# LMAT_AMT_V1.net
KiCad netlist of a schematic drawn in Altium Designer
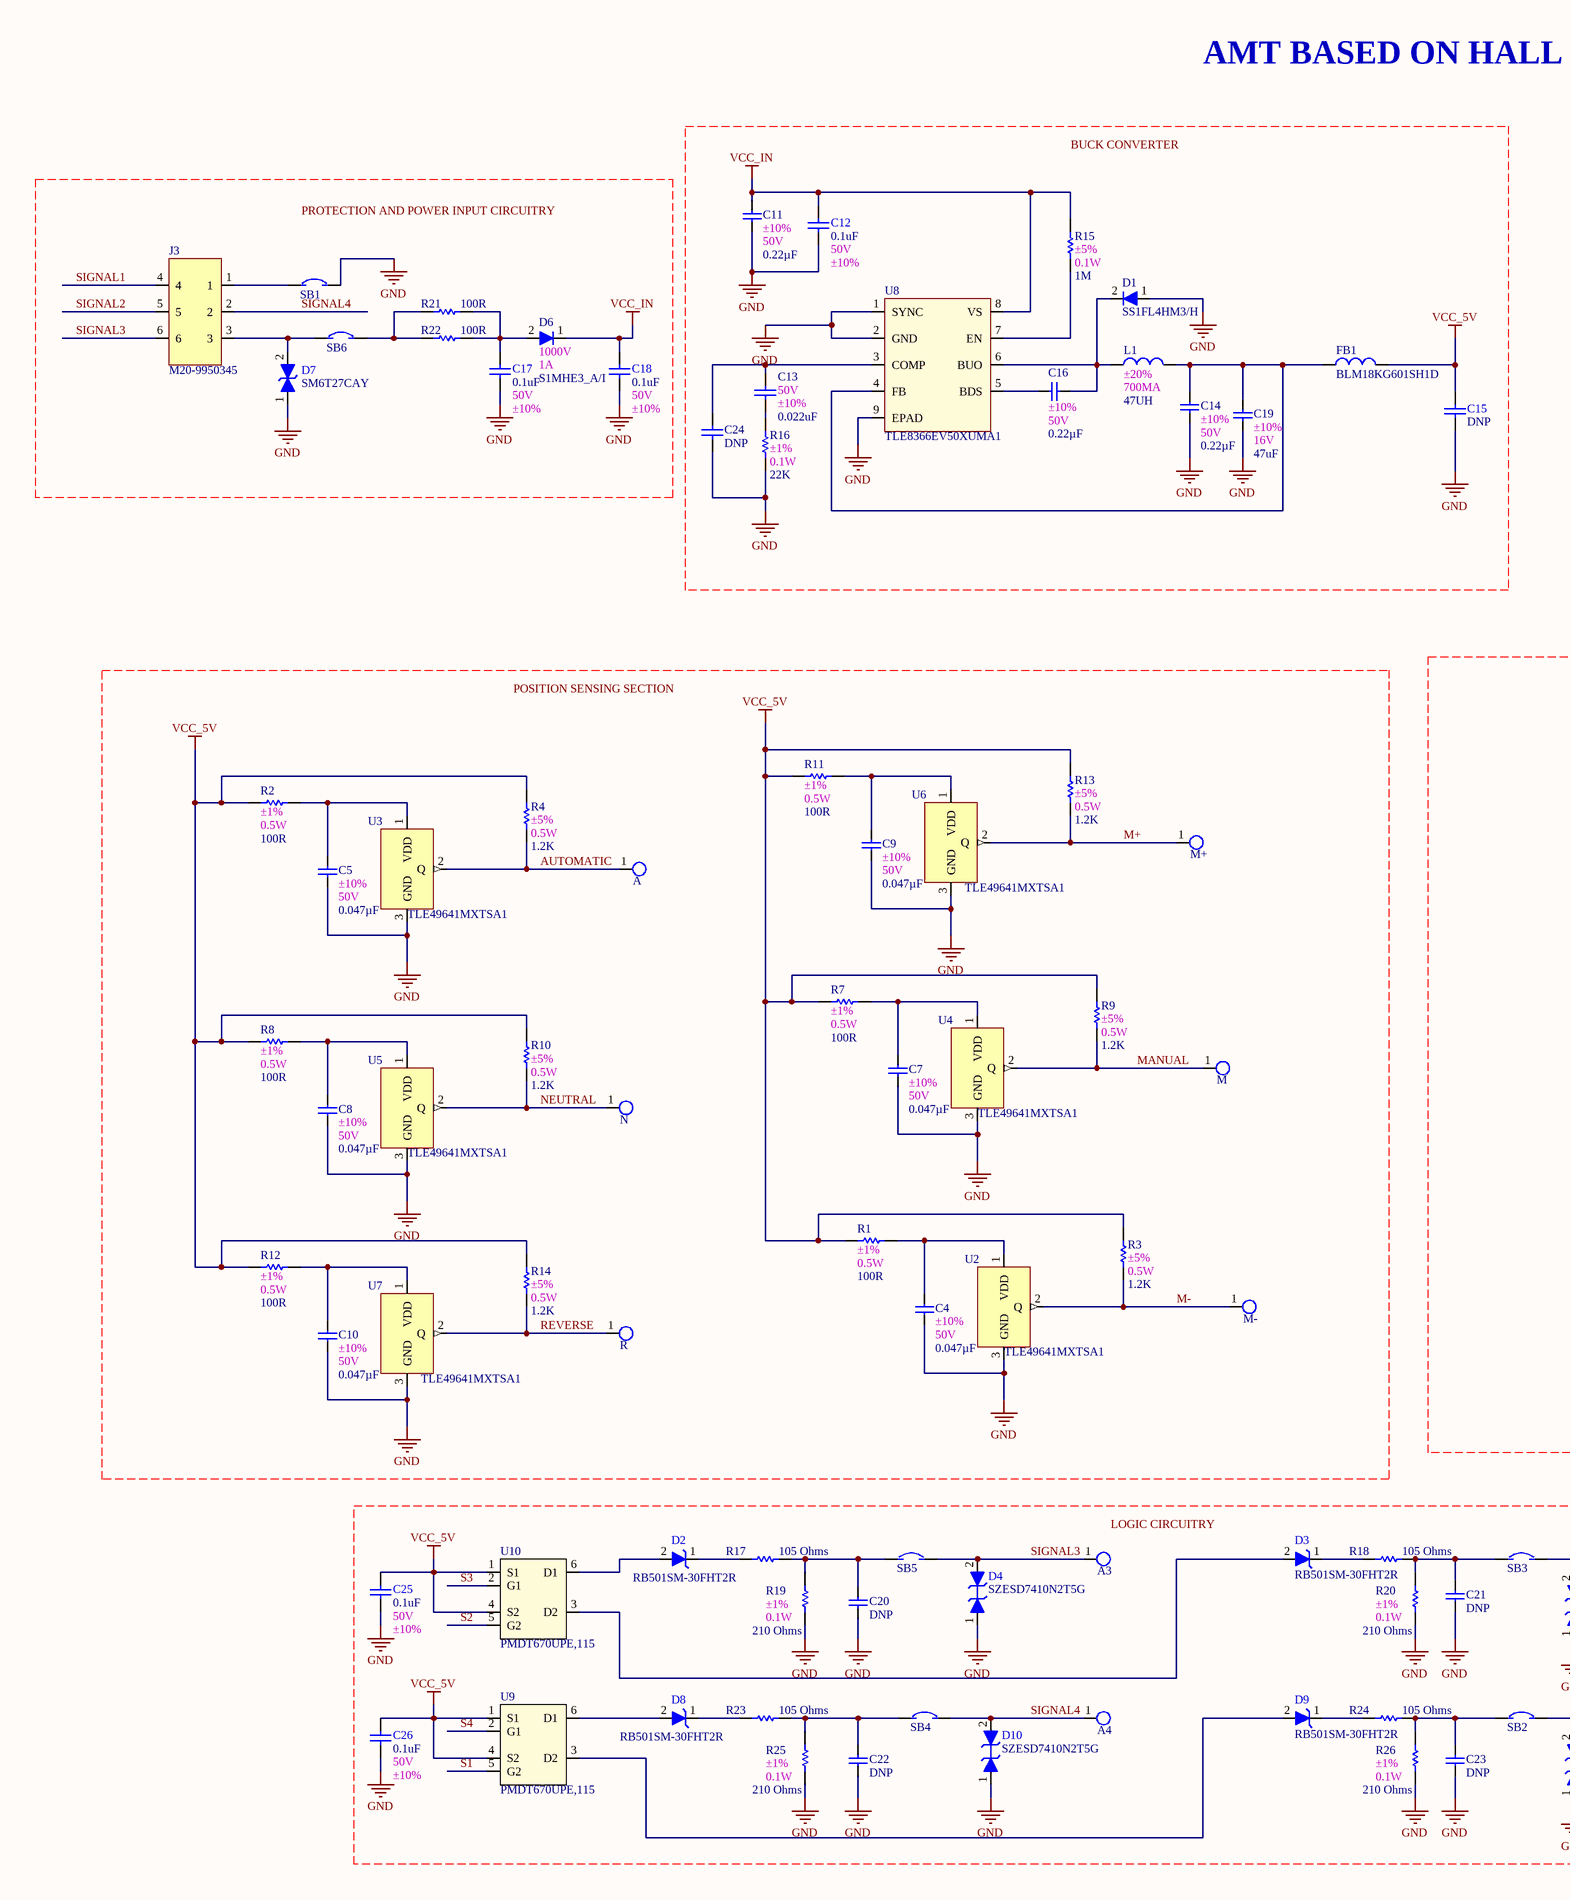
[diagram p0: LMAT_AMT_V1.SchDoc, left]
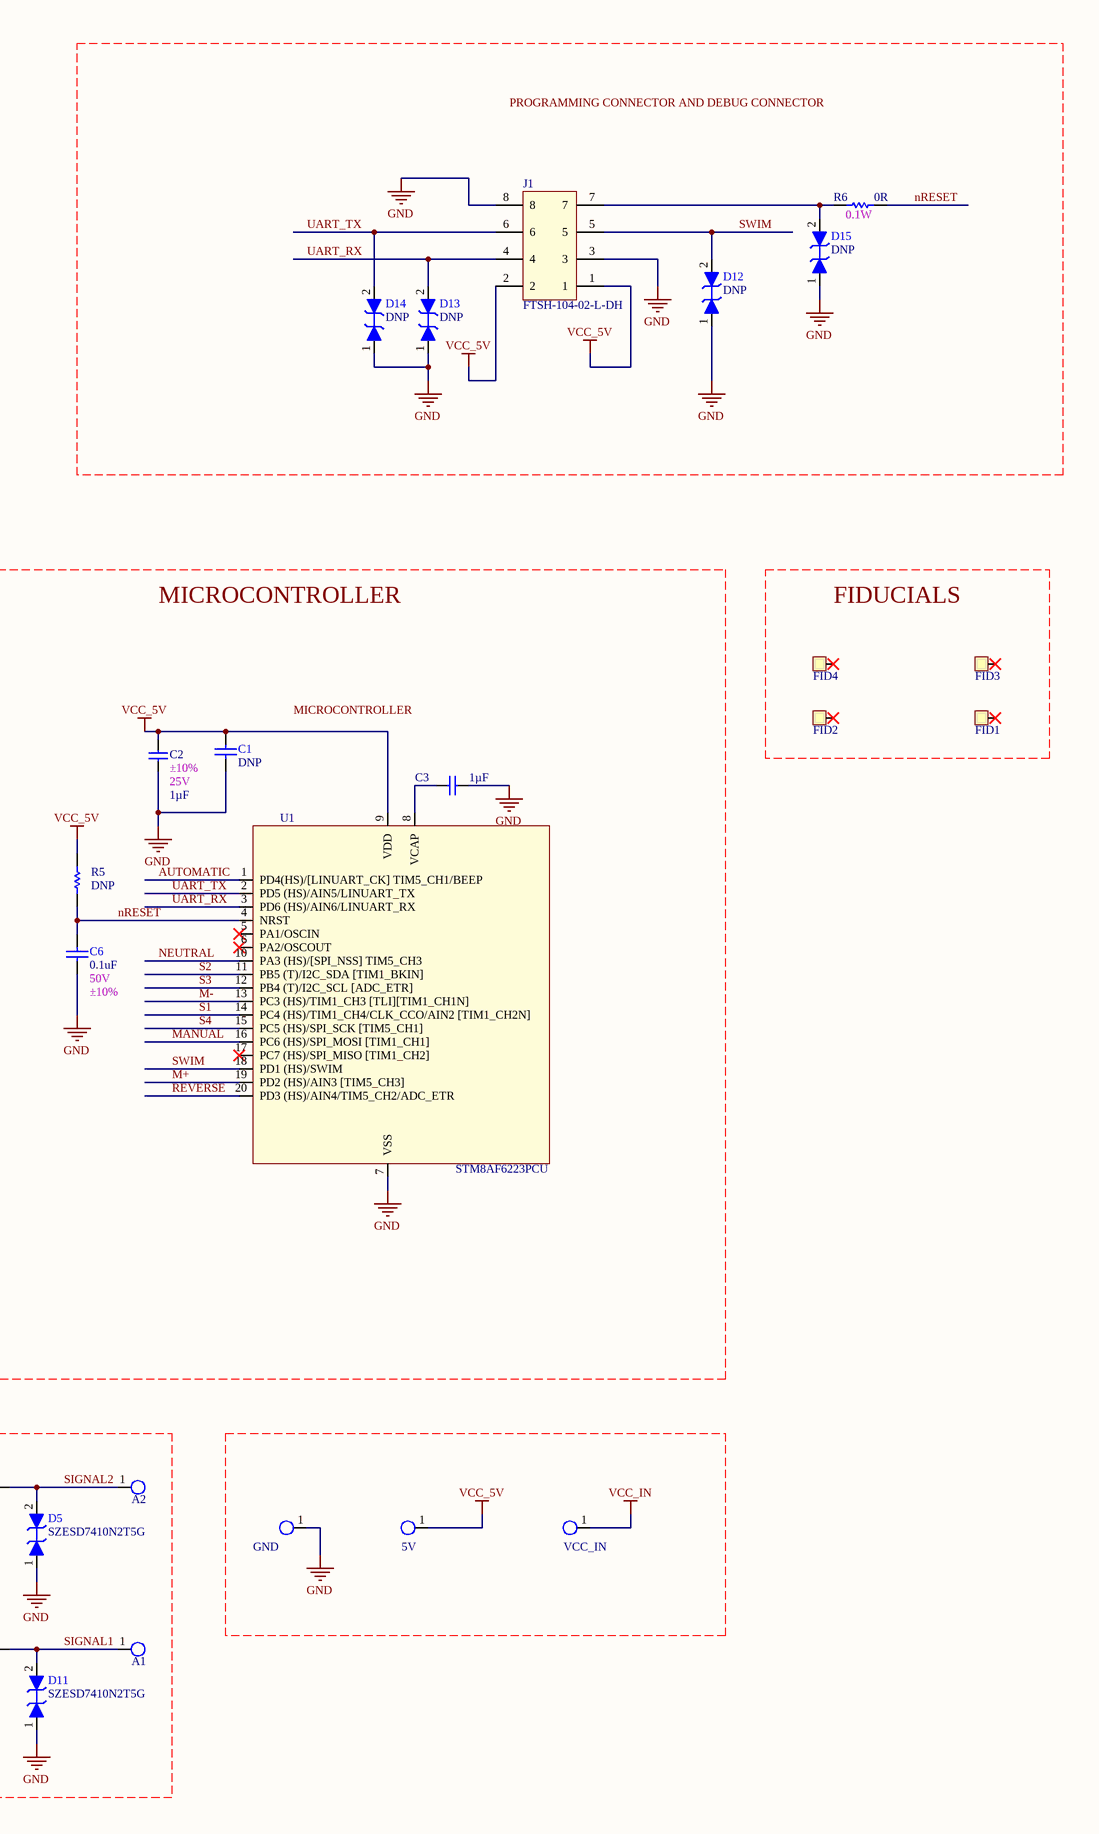
[diagram p1: LMAT_AMT_V1.SchDoc, right]

(export (version "E")
  (design (tool "Eeschema 10.0.6"))
  (components
    (comp (ref "5V")
      (value "Test Point- 35mil")
      (footprint "TP_35M_DIA")
      (fields (field (name "INTERNAL PART NUMBER") "EMS-TP35MIL-S"))
      (libsource (lib "Integrated_Master_Library") (part "EMS-TP35MIL-S"))
    )
    (comp (ref "A")
      (value "Test Point- 35mil")
      (footprint "TP_35M_DIA")
      (fields (field (name "INTERNAL PART NUMBER") "EMS-TP35MIL-S"))
      (libsource (lib "Integrated_Master_Library") (part "EMS-TP35MIL-S"))
    )
    (comp (ref "A1")
      (value "Test Point- 35mil")
      (footprint "TP_35M_DIA")
      (fields (field (name "INTERNAL PART NUMBER") "EMS-TP35MIL-S"))
      (libsource (lib "Integrated_Master_Library") (part "EMS-TP35MIL-S"))
    )
    (comp (ref "A2")
      (value "Test Point- 35mil")
      (footprint "TP_35M_DIA")
      (fields (field (name "INTERNAL PART NUMBER") "EMS-TP35MIL-S"))
      (libsource (lib "Integrated_Master_Library") (part "EMS-TP35MIL-S"))
    )
    (comp (ref "A3")
      (value "Test Point- 35mil")
      (footprint "TP_35M_DIA")
      (fields (field (name "INTERNAL PART NUMBER") "EMS-TP35MIL-S"))
      (libsource (lib "Integrated_Master_Library") (part "EMS-TP35MIL-S"))
    )
    (comp (ref "A4")
      (value "Test Point- 35mil")
      (footprint "TP_35M_DIA")
      (fields (field (name "INTERNAL PART NUMBER") "EMS-TP35MIL-S"))
      (libsource (lib "Integrated_Master_Library") (part "EMS-TP35MIL-S"))
    )
    (comp (ref "C1")
      (value "DNP")
      (footprint "SMDC0603")
      (description "CAP CER 0.1UF 50V 10% X7R 0603")
      (fields
        (field (name "MANUFACTURER PART NUMBER") "CGA3E2X7R1H104K080AA")
        (field (name "MANUFACTURER") "TDK Corporation")
      )
      (libsource (lib "Integrated_Master_Library") (part "ECA0U10K50V0-SC"))
    )
    (comp (ref "C2")
      (value "1µF")
      (footprint "SMDC0603")
      (description "CAP CER 1UF 25V X7R 0603")
      (fields
        (field (name "MANUFACTURER") "TDK Corporation")
        (field (name "VENDOR PART NUMBER") "445-173628-1-ND")
        (field (name "2ND AUXILIARY FIELD") "±10%")
        (field (name "1ST AUXILIARY FIELD") "25V")
      )
      (libsource (lib "Integrated_Master_Library (3)") (part "ECA1U00L25V0-SC"))
    )
    (comp (ref "C3")
      (value "1µF")
      (footprint "SMDC0603")
      (description "CAP CER 1UF 25V X7R 0603")
      (fields
        (field (name "MANUFACTURER") "TDK Corporation")
        (field (name "VENDOR PART NUMBER") "445-173628-1-ND")
      )
      (libsource (lib "Integrated_Master_Library (3)") (part "ECA1U00L25V0-SC"))
    )
    (comp (ref "C4")
      (value "0.047µF")
      (footprint "SMDC0603")
      (description "CAP CER 0.047UF 50V X7R 0603")
      (fields
        (field (name "MANUFACTURER") "TDK Corporation")
        (field (name "VENDOR PART NUMBER") "445-5664-1-ND")
        (field (name "2ND AUXILIARY FIELD") "±10%")
        (field (name "1ST AUXILIARY FIELD") "50V")
      )
      (libsource (lib "Integrated_Master_Library") (part "ECA47N0L50V-SC"))
    )
    (comp (ref "C5")
      (value "0.047µF")
      (footprint "SMDC0603")
      (description "CAP CER 0.047UF 50V X7R 0603")
      (fields
        (field (name "MANUFACTURER") "TDK Corporation")
        (field (name "VENDOR PART NUMBER") "445-5664-1-ND")
        (field (name "2ND AUXILIARY FIELD") "±10%")
        (field (name "1ST AUXILIARY FIELD") "50V")
      )
      (libsource (lib "Integrated_Master_Library") (part "ECA47N0L50V-SC"))
    )
    (comp (ref "C6")
      (value "0.1uF")
      (footprint "SMDC0603")
      (description "CAP CER 0.1UF 50V 10% X7R 0603")
      (fields
        (field (name "MANUFACTURER PART NUMBER") "CGA3E2X7R1H104K080AA")
        (field (name "MANUFACTURER") "TDK Corporation")
        (field (name "1ST AUXILIARY FIELD") "50V")
        (field (name "2ND AUXILIARY FIELD") "±10%")
      )
      (libsource (lib "Integrated_Master_Library") (part "ECA0U10K50V0-SC"))
    )
    (comp (ref "C7")
      (value "0.047µF")
      (footprint "SMDC0603")
      (description "CAP CER 0.047UF 50V X7R 0603")
      (fields
        (field (name "MANUFACTURER") "TDK Corporation")
        (field (name "VENDOR PART NUMBER") "445-5664-1-ND")
        (field (name "2ND AUXILIARY FIELD") "±10%")
        (field (name "1ST AUXILIARY FIELD") "50V")
      )
      (libsource (lib "Integrated_Master_Library") (part "ECA47N0L50V-SC"))
    )
    (comp (ref "C8")
      (value "0.047µF")
      (footprint "SMDC0603")
      (description "CAP CER 0.047UF 50V X7R 0603")
      (fields
        (field (name "MANUFACTURER") "TDK Corporation")
        (field (name "VENDOR PART NUMBER") "445-5664-1-ND")
        (field (name "2ND AUXILIARY FIELD") "±10%")
        (field (name "1ST AUXILIARY FIELD") "50V")
      )
      (libsource (lib "Integrated_Master_Library") (part "ECA47N0L50V-SC"))
    )
    (comp (ref "C9")
      (value "0.047µF")
      (footprint "SMDC0603")
      (description "CAP CER 0.047UF 50V X7R 0603")
      (fields
        (field (name "MANUFACTURER") "TDK Corporation")
        (field (name "VENDOR PART NUMBER") "445-5664-1-ND")
        (field (name "2ND AUXILIARY FIELD") "±10%")
        (field (name "1ST AUXILIARY FIELD") "50V")
      )
      (libsource (lib "Integrated_Master_Library") (part "ECA47N0L50V-SC"))
    )
    (comp (ref "C10")
      (value "0.047µF")
      (footprint "SMDC0603")
      (description "CAP CER 0.047UF 50V X7R 0603")
      (fields
        (field (name "MANUFACTURER") "TDK Corporation")
        (field (name "VENDOR PART NUMBER") "445-5664-1-ND")
        (field (name "2ND AUXILIARY FIELD") "±10%")
        (field (name "1ST AUXILIARY FIELD") "50V")
      )
      (libsource (lib "Integrated_Master_Library") (part "ECA47N0L50V-SC"))
    )
    (comp (ref "C11")
      (value "0.22µF")
      (footprint "SMDC0603")
      (description "CAP CER 0.22UF 50V X7R 0603")
      (fields
        (field (name "MANUFACTURER") "Murata Electronics North America")
        (field (name "VENDOR PART NUMBER") "490-14410-1-ND")
        (field (name "2ND AUXILIARY FIELD") "±10%")
        (field (name "1ST AUXILIARY FIELD") "50V")
      )
      (libsource (lib "Integrated_Master_Library (3)") (part "ECA0U22L50V0-SC"))
    )
    (comp (ref "C12")
      (value "0.1uF")
      (footprint "SMDC0603")
      (description "CAP CER 0.1UF 50V 10% X7R 0603")
      (fields
        (field (name "MANUFACTURER PART NUMBER") "CGA3E2X7R1H104K080AA")
        (field (name "MANUFACTURER") "TDK Corporation")
        (field (name "1ST AUXILIARY FIELD") "50V")
        (field (name "2ND AUXILIARY FIELD") "±10%")
      )
      (libsource (lib "Integrated_Master_Library") (part "ECA0U10K50V0-SC"))
    )
    (comp (ref "C13")
      (value "0.022uF")
      (footprint "SMDC0603")
      (description "CAP CER 0.022UF 50V 10% X7R 0603")
      (fields
        (field (name "MANUFACTURER PART NUMBER") "CGA3E2X7R1H223K080AA")
        (field (name "MANUFACTURER") "TDK Corporation")
        (field (name "1ST AUXILIARY FIELD") "50V")
        (field (name "2ND AUXILIARY FIELD") "±10%")
      )
      (libsource (lib "Integrated_Master_Library") (part "ECA0U022K50V0-SC"))
    )
    (comp (ref "C14")
      (value "0.22µF")
      (footprint "SMDC0603")
      (description "CAP CER 0.22UF 50V X7R 0603")
      (fields
        (field (name "MANUFACTURER") "Murata Electronics North America")
        (field (name "VENDOR PART NUMBER") "490-14410-1-ND")
        (field (name "2ND AUXILIARY FIELD") "±10%")
        (field (name "1ST AUXILIARY FIELD") "50V")
      )
      (libsource (lib "Integrated_Master_Library (3)") (part "ECA0U22L50V0-SC"))
    )
    (comp (ref "C15")
      (value "DNP")
      (footprint "SMDC0603")
      (description "CAP CER 0.1UF 50V 10% X7R 0603")
      (fields
        (field (name "MANUFACTURER PART NUMBER") "CGA3E2X7R1H104K080AA")
        (field (name "MANUFACTURER") "TDK Corporation")
      )
      (libsource (lib "Integrated_Master_Library") (part "ECA0U10K50V0-SC"))
    )
    (comp (ref "C16")
      (value "0.22µF")
      (footprint "SMDC0603")
      (description "CAP CER 0.22UF 50V X7R 0603")
      (fields
        (field (name "MANUFACTURER") "Murata Electronics North America")
        (field (name "VENDOR PART NUMBER") "490-14410-1-ND")
        (field (name "2ND AUXILIARY FIELD") "±10%")
        (field (name "1ST AUXILIARY FIELD") "50V")
      )
      (libsource (lib "Integrated_Master_Library") (part "ECA0U22L50V0-SC"))
    )
    (comp (ref "C17")
      (value "0.1uF")
      (footprint "SMDC0603")
      (description "CAP CER 0.1UF 50V 10% X7R 0603")
      (fields
        (field (name "MANUFACTURER PART NUMBER") "CGA3E2X7R1H104K080AA")
        (field (name "MANUFACTURER") "TDK Corporation")
        (field (name "1ST AUXILIARY FIELD") "50V")
        (field (name "2ND AUXILIARY FIELD") "±10%")
      )
      (libsource (lib "Integrated_Master_Library") (part "ECA0U10K50V0-SC"))
    )
    (comp (ref "C18")
      (value "0.1uF")
      (footprint "SMDC0603")
      (description "CAP CER 0.1UF 50V 10% X7R 0603")
      (fields
        (field (name "MANUFACTURER PART NUMBER") "CGA3E2X7R1H104K080AA")
        (field (name "MANUFACTURER") "TDK Corporation")
        (field (name "1ST AUXILIARY FIELD") "50V")
        (field (name "2ND AUXILIARY FIELD") "±10%")
      )
      (libsource (lib "Integrated_Master_Library") (part "ECA0U10K50V0-SC"))
    )
    (comp (ref "C19")
      (value "47uF")
      (footprint "SMDC1210")
      (description "CAP CER 47UF 16V X6S 1210")
      (fields
        (field (name "MANUFACTURER") "Murata Electronics North America")
        (field (name "VENDOR PART NUMBER") "490-12494-1-ND")
        (field (name "2ND AUXILIARY FIELD") "±10%")
        (field (name "1ST AUXILIARY FIELD") "16V")
      )
      (libsource (lib "Automobile-ML") (part "ECA47U0L16V0-SH"))
    )
    (comp (ref "C20")
      (value "DNP")
      (footprint "SMDC0603")
      (description "CAP CER 10000PF 50V X8R 0603")
      (fields
        (field (name "MANUFACTURER") "TDK Corporation")
        (field (name "VENDOR PART NUMBER") "445-5892-1-ND")
      )
      (libsource (lib "Automobile-ML") (part "ECA0U01L50V0-SC"))
    )
    (comp (ref "C21")
      (value "DNP")
      (footprint "SMDC0603")
      (description "CAP CER 10000PF 50V X8R 0603")
      (fields
        (field (name "MANUFACTURER") "TDK Corporation")
        (field (name "VENDOR PART NUMBER") "445-5892-1-ND")
      )
      (libsource (lib "Automobile-ML") (part "ECA0U01L50V0-SC"))
    )
    (comp (ref "C22")
      (value "DNP")
      (footprint "SMDC0603")
      (description "CAP CER 10000PF 50V X8R 0603")
      (fields
        (field (name "MANUFACTURER") "TDK Corporation")
        (field (name "VENDOR PART NUMBER") "445-5892-1-ND")
      )
      (libsource (lib "Automobile-ML") (part "ECA0U01L50V0-SC"))
    )
    (comp (ref "C23")
      (value "DNP")
      (footprint "SMDC0603")
      (description "CAP CER 10000PF 50V X8R 0603")
      (fields
        (field (name "MANUFACTURER") "TDK Corporation")
        (field (name "VENDOR PART NUMBER") "445-5892-1-ND")
      )
      (libsource (lib "Automobile-ML") (part "ECA0U01L50V0-SC"))
    )
    (comp (ref "C24")
      (value "DNP")
      (footprint "SMDC0603")
      (description "CAP CER 0.022UF 50V 10% X7R 0603")
      (fields
        (field (name "MANUFACTURER PART NUMBER") "CGA3E2X7R1H223K080AA")
        (field (name "MANUFACTURER") "TDK Corporation")
      )
      (libsource (lib "Integrated_Master_Library") (part "ECA0U022K50V0-SC"))
    )
    (comp (ref "C25")
      (value "0.1uF")
      (footprint "SMDC0603")
      (description "CAP CER 0.1UF 50V 10% X7R 0603")
      (fields
        (field (name "MANUFACTURER PART NUMBER") "CGA3E2X7R1H104K080AA")
        (field (name "MANUFACTURER") "TDK Corporation")
        (field (name "1ST AUXILIARY FIELD") "50V")
        (field (name "2ND AUXILIARY FIELD") "±10%")
      )
      (libsource (lib "Integrated_Master_Library") (part "ECA0U10K50V0-SC"))
    )
    (comp (ref "C26")
      (value "0.1uF")
      (footprint "SMDC0603")
      (description "CAP CER 0.1UF 50V 10% X7R 0603")
      (fields
        (field (name "MANUFACTURER PART NUMBER") "CGA3E2X7R1H104K080AA")
        (field (name "MANUFACTURER") "TDK Corporation")
        (field (name "1ST AUXILIARY FIELD") "50V")
        (field (name "2ND AUXILIARY FIELD") "±10%")
      )
      (libsource (lib "Integrated_Master_Library") (part "ECA0U10K50V0-SC"))
    )
    (comp (ref "D1")
      (value "SS1FL4HM3/H")
      (footprint "SODFL370X110-2N")
      (description "DIODE SCHOTTKY 40V 1A DO-219AB")
      (fields
        (field (name "MANUFACTURER") "Vishay Semiconductor Diodes Division")
        (field (name "INTERNAL PART NUMBER") "EDDVS1A0040V0-S")
      )
      (libsource (lib "Integrated_Master_Library (3)") (part "EDDVS1A0040V0-S"))
    )
    (comp (ref "D2")
      (value "RB501SM-30FHT2R")
      (footprint "SOD1700X70N-V2")
      (description "Diode Schottky 30V 100mA Surface Mount EMD2")
      (fields
        (field (name "MANUFACTURER") "Rohm Semiconductor")
        (field (name "INTERNAL PART NUMBER") "EDDR0A1030V0-S")
      )
      (libsource (lib "Integrated_Master_Library (3)") (part "EDDR0A1030V0-S"))
    )
    (comp (ref "D3")
      (value "RB501SM-30FHT2R")
      (footprint "SOD1700X70N-V2")
      (description "Diode Schottky 30V 100mA Surface Mount EMD2")
      (fields
        (field (name "MANUFACTURER") "Rohm Semiconductor")
        (field (name "INTERNAL PART NUMBER") "EDDR0A1030V0-S")
      )
      (libsource (lib "Integrated_Master_Library (3)") (part "EDDR0A1030V0-S"))
    )
    (comp (ref "D4")
      (value "SZESD7410N2T5G")
      (footprint "DFN65P100X65X45-2N")
      (description "TVS DIODE 8V 20V 2X2DFN")
      (fields
        (field (name "MANUFACTURER") "ON Semiconductor")
        (field (name "INTERNAL PART NUMBER") "EDDOS16A010V0-S")
      )
      (libsource (lib "Automobile-ML") (part "EDDOS16A010V0-S"))
    )
    (comp (ref "D5")
      (value "SZESD7410N2T5G")
      (footprint "DFN65P100X65X45-2N")
      (description "TVS DIODE 8V 20V 2X2DFN")
      (fields
        (field (name "MANUFACTURER") "ON Semiconductor")
        (field (name "INTERNAL PART NUMBER") "EDDOS16A010V0-S")
      )
      (libsource (lib "Automobile-ML") (part "EDDOS16A010V0-S"))
    )
    (comp (ref "D6")
      (value "S1MHE3_A/I")
      (footprint "DIOM4227X23N-2N")
      (description "DIODE GEN PURP 1KV 1A DO214AC")
      (fields
        (field (name "MANUFACTURER") "Vishay Semiconductor Diodes Division")
        (field (name "INTERNAL PART NUMBER") "EDDVS1A001000V-S")
        (field (name "1ST AUXILIARY FIELD") "1000V")
        (field (name "2ND AUXILIARY FIELD") "1A")
      )
      (libsource (lib "Integrated_Master_Library") (part "EDDVS1A001000V-S"))
    )
    (comp (ref "D7")
      (value "SM6T27CAY")
      (footprint "DIOM4336X26B")
      (description "TVS DIODE 23.1V 48.3V SMB")
      (fields
        (field (name "MANUFACTURER") "STMicroelectronics")
        (field (name "INTERNAL PART NUMBER") "EDDST83A025V7-S")
      )
      (libsource (lib "Integrated_Master_Library") (part "EDDST83A025V7-S"))
    )
    (comp (ref "D8")
      (value "RB501SM-30FHT2R")
      (footprint "SOD1700X70N-V2")
      (description "Diode Schottky 30V 100mA Surface Mount EMD2")
      (fields
        (field (name "MANUFACTURER") "Rohm Semiconductor")
        (field (name "INTERNAL PART NUMBER") "EDDR0A1030V0-S")
      )
      (libsource (lib "Integrated_Master_Library (3)") (part "EDDR0A1030V0-S"))
    )
    (comp (ref "D9")
      (value "RB501SM-30FHT2R")
      (footprint "SOD1700X70N-V2")
      (description "Diode Schottky 30V 100mA Surface Mount EMD2")
      (fields
        (field (name "MANUFACTURER") "Rohm Semiconductor")
        (field (name "INTERNAL PART NUMBER") "EDDR0A1030V0-S")
      )
      (libsource (lib "Integrated_Master_Library (3)") (part "EDDR0A1030V0-S"))
    )
    (comp (ref "D10")
      (value "SZESD7410N2T5G")
      (footprint "DFN65P100X65X45-2N")
      (description "TVS DIODE 8V 20V 2X2DFN")
      (fields
        (field (name "MANUFACTURER") "ON Semiconductor")
        (field (name "INTERNAL PART NUMBER") "EDDOS16A010V0-S")
      )
      (libsource (lib "Automobile-ML") (part "EDDOS16A010V0-S"))
    )
    (comp (ref "D11")
      (value "SZESD7410N2T5G")
      (footprint "DFN65P100X65X45-2N")
      (description "TVS DIODE 8V 20V 2X2DFN")
      (fields
        (field (name "MANUFACTURER") "ON Semiconductor")
        (field (name "INTERNAL PART NUMBER") "EDDOS16A010V0-S")
      )
      (libsource (lib "Automobile-ML") (part "EDDOS16A010V0-S"))
    )
    (comp (ref "D12")
      (value "DNP")
      (footprint "DFN65P100X65X45-2N")
      (description "TVS DIODE 8V 20V 2X2DFN")
      (fields
        (field (name "MANUFACTURER PART NUMBER") "SZESD7410N2T5G")
        (field (name "MANUFACTURER") "ON Semiconductor")
      )
      (libsource (lib "Automobile-ML") (part "EDDOS16A010V0-S"))
    )
    (comp (ref "D13")
      (value "DNP")
      (footprint "DFN65P100X65X45-2N")
      (description "TVS DIODE 8V 20V 2X2DFN")
      (fields
        (field (name "MANUFACTURER PART NUMBER") "SZESD7410N2T5G")
        (field (name "MANUFACTURER") "ON Semiconductor")
      )
      (libsource (lib "Automobile-ML") (part "EDDOS16A010V0-S"))
    )
    (comp (ref "D14")
      (value "DNP")
      (footprint "DFN65P100X65X45-2N")
      (description "TVS DIODE 8V 20V 2X2DFN")
      (fields
        (field (name "MANUFACTURER PART NUMBER") "SZESD7410N2T5G")
        (field (name "MANUFACTURER") "ON Semiconductor")
      )
      (libsource (lib "Automobile-ML") (part "EDDOS16A010V0-S"))
    )
    (comp (ref "D15")
      (value "DNP")
      (footprint "DFN65P100X65X45-2N")
      (description "TVS DIODE 8V 20V 2X2DFN")
      (fields
        (field (name "MANUFACTURER PART NUMBER") "SZESD7410N2T5G")
        (field (name "MANUFACTURER") "ON Semiconductor")
      )
      (libsource (lib "Automobile-ML") (part "EDDOS16A010V0-S"))
    )
    (comp (ref "FB1")
      (value "BLM18KG601SH1D")
      (footprint "SMDL0603")
      (description "FERRITE BEAD 600 OHM 0603 1LN")
      (fields
        (field (name "MANUFACTURER") "Murata Electronics North America")
        (field (name "VENDOR PART NUMBER") "490-13259-1-ND")
      )
      (libsource (lib "Automobile-ML") (part "EIN600R1A30-S"))
    )
    (comp (ref "FID1")
      (value "FID40X40")
      (footprint "FID40X40")
      (libsource (lib "Integrated_Master_Library") (part "FID_40X40"))
    )
    (comp (ref "FID2")
      (value "FID40X40")
      (footprint "FID40X40")
      (libsource (lib "Integrated_Master_Library") (part "FID_40X40"))
    )
    (comp (ref "FID3")
      (value "FID40X40")
      (footprint "FID40X40")
      (libsource (lib "Integrated_Master_Library") (part "FID_40X40"))
    )
    (comp (ref "FID4")
      (value "FID40X40")
      (footprint "FID40X40")
      (libsource (lib "Integrated_Master_Library") (part "FID_40X40"))
    )
    (comp (ref "GND")
      (value "Test Point- 35mil")
      (footprint "TP_35M_DIA")
      (fields (field (name "INTERNAL PART NUMBER") "EMS-TP35MIL-S"))
      (libsource (lib "Integrated_Master_Library") (part "EMS-TP35MIL-S"))
    )
    (comp (ref "J1")
      (value "CONN HEADER R/A 6POS 2.54MMCONN HEADER SMD R/A 8POS 1.27MM")
      (footprint "HDRRA8W53P127_2X4_9754X251X343P")
      (description "CONN HEADER SMD R/A 8POS 1.27MM")
      (fields
        (field (name "MANUFACTURER") "Samtec Inc.")
        (field (name "INTERNAL PART NUMBER") "ECN-FTSH-104-02-L-DH-0005")
        (field (name "MANUFACTURER PART NUMBER") "FTSH-104-02-L-DH")
      )
      (libsource (lib "Automobile-ML") (part "ECN-FTSH-104-02-L-DH-0005"))
    )
    (comp (ref "J3")
      (value "CONN HEADER R/A 6POS 2.54MM")
      (footprint "HDRRA6W86P254_2X3_1344X254X528P")
      (fields
        (field (name "MANUFACTURER") "Harwin Inc.")
        (field (name "INTERNAL PART NUMBER") "ECN-M20-9950345-0003")
        (field (name "VENDOR PART NUMBER") "952-2092-ND")
        (field (name "MANUFACTURER PART NUMBER") "M20-9950345")
      )
      (libsource (lib "Automobile-ML") (part "ECN-M20-9950345-0003"))
    )
    (comp (ref "L1")
      (value "47UH")
      (footprint "INDP5050X20N")
      (description "FIXED IND 47UH 700MA 460MOHM SMD")
      (fields
        (field (name "MANUFACTURER") "Bourns Inc.")
        (field (name "VENDOR PART NUMBER") "SRN5020TA-470MCT-ND")
        (field (name "2ND AUXILIARY FIELD") "±20%")
        (field (name "1ST AUXILIARY FIELD") "700MA")
      )
      (libsource (lib "Automobile-ML") (part "EIN47U0N700M-S"))
    )
    (comp (ref "M")
      (value "Test Point- 35mil")
      (footprint "TP_35M_DIA")
      (fields (field (name "INTERNAL PART NUMBER") "EMS-TP35MIL-S"))
      (libsource (lib "Integrated_Master_Library") (part "EMS-TP35MIL-S"))
    )
    (comp (ref "M+")
      (value "Test Point- 35mil")
      (footprint "TP_35M_DIA")
      (fields (field (name "INTERNAL PART NUMBER") "EMS-TP35MIL-S"))
      (libsource (lib "Integrated_Master_Library") (part "EMS-TP35MIL-S"))
    )
    (comp (ref "M-")
      (value "Test Point- 35mil")
      (footprint "TP_35M_DIA")
      (fields (field (name "INTERNAL PART NUMBER") "EMS-TP35MIL-S"))
      (libsource (lib "Integrated_Master_Library") (part "EMS-TP35MIL-S"))
    )
    (comp (ref "N")
      (value "Test Point- 35mil")
      (footprint "TP_35M_DIA")
      (fields (field (name "INTERNAL PART NUMBER") "EMS-TP35MIL-S"))
      (libsource (lib "Integrated_Master_Library") (part "EMS-TP35MIL-S"))
    )
    (comp (ref "R")
      (value "Test Point- 35mil")
      (footprint "TP_35M_DIA")
      (fields (field (name "INTERNAL PART NUMBER") "EMS-TP35MIL-S"))
      (libsource (lib "Integrated_Master_Library") (part "EMS-TP35MIL-S"))
    )
    (comp (ref "R1")
      (value "100R")
      (footprint "SMDR0805")
      (description "RES SMD 100 OHM 1% 1/2W 0805")
      (fields
        (field (name "MANUFACTURER PART NUMBER") "ERJ-P6WF1000V")
        (field (name "MANUFACTURER") "Panasonic Electronic Components")
        (field (name "2ND AUXILIARY FIELD") "±1%")
        (field (name "1ST AUXILIARY FIELD") "0.5W")
      )
      (libsource (lib "Integrated_Master_Library") (part "ERE100RG102-SE"))
    )
    (comp (ref "R2")
      (value "100R")
      (footprint "SMDR0805")
      (description "RES SMD 100 OHM 1% 1/2W 0805")
      (fields
        (field (name "MANUFACTURER PART NUMBER") "ERJ-P6WF1000V")
        (field (name "MANUFACTURER") "Panasonic Electronic Components")
        (field (name "2ND AUXILIARY FIELD") "±1%")
        (field (name "1ST AUXILIARY FIELD") "0.5W")
      )
      (libsource (lib "Integrated_Master_Library") (part "ERE100RG102-SE"))
    )
    (comp (ref "R3")
      (value "1.2K")
      (footprint "SMDR0805")
      (description "RES SMD 1.2K OHM 5% 1/2W 0805")
      (fields
        (field (name "MANUFACTURER") "Panasonic Electronic Components")
        (field (name "VENDOR PART NUMBER") "P1.2KADCT-ND")
        (field (name "2ND AUXILIARY FIELD") "±5%")
        (field (name "1ST AUXILIARY FIELD") "0.5W")
      )
      (libsource (lib "Integrated_Master_Library") (part "ERE1K20G102-SE"))
    )
    (comp (ref "R4")
      (value "1.2K")
      (footprint "SMDR0805")
      (description "RES SMD 1.2K OHM 5% 1/2W 0805")
      (fields
        (field (name "MANUFACTURER") "Panasonic Electronic Components")
        (field (name "VENDOR PART NUMBER") "P1.2KADCT-ND")
        (field (name "2ND AUXILIARY FIELD") "±5%")
        (field (name "1ST AUXILIARY FIELD") "0.5W")
      )
      (libsource (lib "Integrated_Master_Library") (part "ERE1K20G102-SE"))
    )
    (comp (ref "R5")
      (value "DNP")
      (footprint "SMDR0603")
      (description "RES SMD 47K OHM 1% 1/10W 0603")
      (fields (field (name "MANUFACTURER") "Yageo") (field (name "VENDOR PART NUMBER") "YAG2129CT-ND"))
      (libsource (lib "Integrated_Master_Library (3)") (part "ERE47K0G110-SC"))
    )
    (comp (ref "R6")
      (value "0R")
      (footprint "SMDR0603")
      (description "RES SMD 0.0OHM JUMPER 1/10W 0603")
      (fields
        (field (name "MANUFACTURER PART NUMBER") "ERJ-3GEY0R00V")
        (field (name "MANUFACTURER") "Panasonic Electronic Components")
        (field (name "1ST AUXILIARY FIELD") "0.1W")
      )
      (libsource (lib "Integrated_Master_Library") (part "ERE0R00110-SC"))
    )
    (comp (ref "R7")
      (value "100R")
      (footprint "SMDR0805")
      (description "RES SMD 100 OHM 1% 1/2W 0805")
      (fields
        (field (name "MANUFACTURER PART NUMBER") "ERJ-P6WF1000V")
        (field (name "MANUFACTURER") "Panasonic Electronic Components")
        (field (name "2ND AUXILIARY FIELD") "±1%")
        (field (name "1ST AUXILIARY FIELD") "0.5W")
      )
      (libsource (lib "Integrated_Master_Library") (part "ERE100RG102-SE"))
    )
    (comp (ref "R8")
      (value "100R")
      (footprint "SMDR0805")
      (description "RES SMD 100 OHM 1% 1/2W 0805")
      (fields
        (field (name "MANUFACTURER PART NUMBER") "ERJ-P6WF1000V")
        (field (name "MANUFACTURER") "Panasonic Electronic Components")
        (field (name "2ND AUXILIARY FIELD") "±1%")
        (field (name "1ST AUXILIARY FIELD") "0.5W")
      )
      (libsource (lib "Integrated_Master_Library") (part "ERE100RG102-SE"))
    )
    (comp (ref "R9")
      (value "1.2K")
      (footprint "SMDR0805")
      (description "RES SMD 1.2K OHM 5% 1/2W 0805")
      (fields
        (field (name "MANUFACTURER") "Panasonic Electronic Components")
        (field (name "VENDOR PART NUMBER") "P1.2KADCT-ND")
        (field (name "2ND AUXILIARY FIELD") "±5%")
        (field (name "1ST AUXILIARY FIELD") "0.5W")
      )
      (libsource (lib "Integrated_Master_Library") (part "ERE1K20G102-SE"))
    )
    (comp (ref "R10")
      (value "1.2K")
      (footprint "SMDR0805")
      (description "RES SMD 1.2K OHM 5% 1/2W 0805")
      (fields
        (field (name "MANUFACTURER") "Panasonic Electronic Components")
        (field (name "VENDOR PART NUMBER") "P1.2KADCT-ND")
        (field (name "2ND AUXILIARY FIELD") "±5%")
        (field (name "1ST AUXILIARY FIELD") "0.5W")
      )
      (libsource (lib "Integrated_Master_Library") (part "ERE1K20G102-SE"))
    )
    (comp (ref "R11")
      (value "100R")
      (footprint "SMDR0805")
      (description "RES SMD 100 OHM 1% 1/2W 0805")
      (fields
        (field (name "MANUFACTURER PART NUMBER") "ERJ-P6WF1000V")
        (field (name "MANUFACTURER") "Panasonic Electronic Components")
        (field (name "2ND AUXILIARY FIELD") "±1%")
        (field (name "1ST AUXILIARY FIELD") "0.5W")
      )
      (libsource (lib "Integrated_Master_Library") (part "ERE100RG102-SE"))
    )
    (comp (ref "R12")
      (value "100R")
      (footprint "SMDR0805")
      (description "RES SMD 100 OHM 1% 1/2W 0805")
      (fields
        (field (name "MANUFACTURER PART NUMBER") "ERJ-P6WF1000V")
        (field (name "MANUFACTURER") "Panasonic Electronic Components")
        (field (name "2ND AUXILIARY FIELD") "±1%")
        (field (name "1ST AUXILIARY FIELD") "0.5W")
      )
      (libsource (lib "Integrated_Master_Library") (part "ERE100RG102-SE"))
    )
    (comp (ref "R13")
      (value "1.2K")
      (footprint "SMDR0805")
      (description "RES SMD 1.2K OHM 5% 1/2W 0805")
      (fields
        (field (name "MANUFACTURER") "Panasonic Electronic Components")
        (field (name "VENDOR PART NUMBER") "P1.2KADCT-ND")
        (field (name "2ND AUXILIARY FIELD") "±5%")
        (field (name "1ST AUXILIARY FIELD") "0.5W")
      )
      (libsource (lib "Integrated_Master_Library") (part "ERE1K20G102-SE"))
    )
    (comp (ref "R14")
      (value "1.2K")
      (footprint "SMDR0805")
      (description "RES SMD 1.2K OHM 5% 1/2W 0805")
      (fields
        (field (name "MANUFACTURER") "Panasonic Electronic Components")
        (field (name "VENDOR PART NUMBER") "P1.2KADCT-ND")
        (field (name "2ND AUXILIARY FIELD") "±5%")
        (field (name "1ST AUXILIARY FIELD") "0.5W")
      )
      (libsource (lib "Integrated_Master_Library") (part "ERE1K20G102-SE"))
    )
    (comp (ref "R15")
      (value "1M")
      (footprint "SMDR0603")
      (description "RES SMD 1M OHM 5% 1/10W 0603")
      (fields
        (field (name "MANUFACTURER") "Vishay Dale")
        (field (name "VENDOR PART NUMBER") "541-2216-1-ND")
        (field (name "2ND AUXILIARY FIELD") "±5%")
        (field (name "1ST AUXILIARY FIELD") "0.1W")
      )
      (libsource (lib "Automobile-ML") (part "ERE1M00K110-SC"))
    )
    (comp (ref "R16")
      (value "22K")
      (footprint "SMDR0603")
      (description "RES SMD 22K OHM 1% 1/10W 0603")
      (fields
        (field (name "MANUFACTURER") "Panasonic Electronic Components")
        (field (name "VENDOR PART NUMBER") "P22.0KHCT-ND")
        (field (name "2ND AUXILIARY FIELD") "±1%")
        (field (name "1ST AUXILIARY FIELD") "0.1W")
      )
      (libsource (lib "Automobile-ML") (part "ERE22K0G110-SC"))
    )
    (comp (ref "R17")
      (value "105 Ohms")
      (footprint "SMDR0603")
      (description "RES SMD 105 OHM 1% 1/10W 0603")
      (fields
        (field (name "MANUFACTURER") "Panasonic Electronic Components")
        (field (name "VENDOR PART NUMBER") "P105HCT-ND")
      )
      (libsource (lib "Automobile-ML") (part "ERE105RG110-SC"))
    )
    (comp (ref "R18")
      (value "105 Ohms")
      (footprint "SMDR0603")
      (description "RES SMD 105 OHM 1% 1/10W 0603")
      (fields
        (field (name "MANUFACTURER") "Panasonic Electronic Components")
        (field (name "VENDOR PART NUMBER") "P105HCT-ND")
      )
      (libsource (lib "Automobile-ML") (part "ERE105RG110-SC"))
    )
    (comp (ref "R19")
      (value "210 Ohms")
      (footprint "SMDR0603")
      (description "RES SMD 210 OHM 1% 1/10W 0603")
      (fields
        (field (name "MANUFACTURER") "Panasonic Electronic Components")
        (field (name "VENDOR PART NUMBER") "P210HCT-ND")
        (field (name "2ND AUXILIARY FIELD") "±1%")
        (field (name "1ST AUXILIARY FIELD") "0.1W")
      )
      (libsource (lib "Automobile-ML") (part "ERE210RG110-SC"))
    )
    (comp (ref "R20")
      (value "210 Ohms")
      (footprint "SMDR0603")
      (description "RES SMD 210 OHM 1% 1/10W 0603")
      (fields
        (field (name "MANUFACTURER") "Panasonic Electronic Components")
        (field (name "VENDOR PART NUMBER") "P210HCT-ND")
        (field (name "2ND AUXILIARY FIELD") "±1%")
        (field (name "1ST AUXILIARY FIELD") "0.1W")
      )
      (libsource (lib "Automobile-ML") (part "ERE210RG110-SC"))
    )
    (comp (ref "R21")
      (value "100R")
      (footprint "RESMELF5922N")
      (description "RES 100 OHM 1% 1W MELF 0207")
      (fields
        (field (name "MANUFACTURER") "Stackpole Electronics Inc")
        (field (name "VENDOR PART NUMBER") "MLFA1FTC100RCT-ND")
      )
      (libsource (lib "Integrated_Master_Library") (part "ERE100RG100-S"))
    )
    (comp (ref "R22")
      (value "100R")
      (footprint "RESMELF5922N")
      (description "RES 100 OHM 1% 1W MELF 0207")
      (fields
        (field (name "MANUFACTURER") "Stackpole Electronics Inc")
        (field (name "VENDOR PART NUMBER") "MLFA1FTC100RCT-ND")
      )
      (libsource (lib "Integrated_Master_Library") (part "ERE100RG100-S"))
    )
    (comp (ref "R23")
      (value "105 Ohms")
      (footprint "SMDR0603")
      (description "RES SMD 105 OHM 1% 1/10W 0603")
      (fields
        (field (name "MANUFACTURER") "Panasonic Electronic Components")
        (field (name "VENDOR PART NUMBER") "P105HCT-ND")
      )
      (libsource (lib "Automobile-ML") (part "ERE105RG110-SC"))
    )
    (comp (ref "R24")
      (value "105 Ohms")
      (footprint "SMDR0603")
      (description "RES SMD 105 OHM 1% 1/10W 0603")
      (fields
        (field (name "MANUFACTURER") "Panasonic Electronic Components")
        (field (name "VENDOR PART NUMBER") "P105HCT-ND")
      )
      (libsource (lib "Automobile-ML") (part "ERE105RG110-SC"))
    )
    (comp (ref "R25")
      (value "210 Ohms")
      (footprint "SMDR0603")
      (description "RES SMD 210 OHM 1% 1/10W 0603")
      (fields
        (field (name "MANUFACTURER") "Panasonic Electronic Components")
        (field (name "VENDOR PART NUMBER") "P210HCT-ND")
        (field (name "2ND AUXILIARY FIELD") "±1%")
        (field (name "1ST AUXILIARY FIELD") "0.1W")
      )
      (libsource (lib "Automobile-ML") (part "ERE210RG110-SC"))
    )
    (comp (ref "R26")
      (value "210 Ohms")
      (footprint "SMDR0603")
      (description "RES SMD 210 OHM 1% 1/10W 0603")
      (fields
        (field (name "MANUFACTURER") "Panasonic Electronic Components")
        (field (name "VENDOR PART NUMBER") "P210HCT-ND")
        (field (name "2ND AUXILIARY FIELD") "±1%")
        (field (name "1ST AUXILIARY FIELD") "0.1W")
      )
      (libsource (lib "Automobile-ML") (part "ERE210RG110-SC"))
    )
    (comp (ref "SB1") (value "EMS_SB20") (footprint "SB_20") (libsource (lib "AMT") (part "EMS_SB20")))
    (comp (ref "SB2") (value "EMS_SB10") (footprint "SB_10") (libsource (lib "AMT") (part "EMS_SB10")))
    (comp (ref "SB3") (value "EMS_SB10") (footprint "SB_10") (libsource (lib "AMT") (part "EMS_SB10")))
    (comp (ref "SB4") (value "EMS_SB10") (footprint "SB_10") (libsource (lib "AMT") (part "EMS_SB10")))
    (comp (ref "SB5") (value "EMS_SB10") (footprint "SB_10") (libsource (lib "AMT") (part "EMS_SB10")))
    (comp (ref "SB6") (value "EMS_SB20") (footprint "SB_20") (libsource (lib "AMT") (part "EMS_SB20")))
    (comp (ref "U1")
      (value "STM8AF6223PCU")
      (footprint "SOP65P640X120-20N")
      (description "IC MCU 8BIT 8KB FLASH 20TSSOP")
      (fields
        (field (name "MANUFACTURER") "STMicroelectronics")
        (field (name "INTERNAL PART NUMBER") "EICSTMTSSOP-20-1691")
      )
      (libsource (lib "Integrated_Master_Library (3)") (part "EICSTMTSSOP-20-1691"))
    )
    (comp (ref "U2")
      (value "TLE49641MXTSA1")
      (footprint "SOT95P248X115-3N")
      (description "MAGNETIC SWITCH UNIPOLAR SOT23-3")
      (fields
        (field (name "MANUFACTURER") "Infineon Technologies")
        (field (name "VENDOR PART NUMBER") "TLE49641MXTSA1CT-ND")
      )
      (libsource (lib "Integrated_Master_Library") (part "EICITSOT23-3-1528"))
    )
    (comp (ref "U3")
      (value "TLE49641MXTSA1")
      (footprint "SOT95P248X115-3N")
      (description "MAGNETIC SWITCH UNIPOLAR SOT23-3")
      (fields
        (field (name "MANUFACTURER") "Infineon Technologies")
        (field (name "VENDOR PART NUMBER") "TLE49641MXTSA1CT-ND")
      )
      (libsource (lib "Integrated_Master_Library") (part "EICITSOT23-3-1528"))
    )
    (comp (ref "U4")
      (value "TLE49641MXTSA1")
      (footprint "SOT95P248X115-3N")
      (description "MAGNETIC SWITCH UNIPOLAR SOT23-3")
      (fields
        (field (name "MANUFACTURER") "Infineon Technologies")
        (field (name "VENDOR PART NUMBER") "TLE49641MXTSA1CT-ND")
      )
      (libsource (lib "Integrated_Master_Library") (part "EICITSOT23-3-1528"))
    )
    (comp (ref "U5")
      (value "TLE49641MXTSA1")
      (footprint "SOT95P248X115-3N")
      (description "MAGNETIC SWITCH UNIPOLAR SOT23-3")
      (fields
        (field (name "MANUFACTURER") "Infineon Technologies")
        (field (name "VENDOR PART NUMBER") "TLE49641MXTSA1CT-ND")
      )
      (libsource (lib "Integrated_Master_Library") (part "EICITSOT23-3-1528"))
    )
    (comp (ref "U6")
      (value "TLE49641MXTSA1")
      (footprint "SOT95P248X115-3N")
      (description "MAGNETIC SWITCH UNIPOLAR SOT23-3")
      (fields
        (field (name "MANUFACTURER") "Infineon Technologies")
        (field (name "VENDOR PART NUMBER") "TLE49641MXTSA1CT-ND")
      )
      (libsource (lib "Integrated_Master_Library") (part "EICITSOT23-3-1528"))
    )
    (comp (ref "U7")
      (value "TLE49641MXTSA1")
      (footprint "SOT95P248X115-3N")
      (description "MAGNETIC SWITCH UNIPOLAR SOT23-3")
      (fields
        (field (name "MANUFACTURER") "Infineon Technologies")
        (field (name "VENDOR PART NUMBER") "TLE49641MXTSA1CT-ND")
      )
      (libsource (lib "Integrated_Master_Library") (part "EICITSOT23-3-1528"))
    )
    (comp (ref "U8")
      (value "TLE8366EV50XUMA1")
      (footprint "SOIC127P600X170_HS-9N")
      (description "IC REG BUCK 5V 1.8A 8DSO")
      (fields
        (field (name "MANUFACTURER") "Infineon Technologies")
        (field (name "INTERNAL PART NUMBER") "EICITSOIC-08-0001")
      )
      (libsource (lib "Automobile-ML") (part "EICITSOIC-08-0001"))
    )
    (comp (ref "U9")
      (value "PMDT670UPE,115")
      (footprint "SOTFL50P160X60-6N")
      (description "MOSFET 2P-CH 20V 0.55A SOT666")
      (fields
        (field (name "MANUFACTURER") "Nexperia USA Inc.")
        (field (name "INTERNAL PART NUMBER") "EICNUSOT666-06-0004")
      )
      (libsource (lib "Automobile-ML") (part "EICNUSOT666-06-0004"))
    )
    (comp (ref "U10")
      (value "PMDT670UPE,115")
      (footprint "SOTFL50P160X60-6N")
      (description "MOSFET 2P-CH 20V 0.55A SOT666")
      (fields
        (field (name "MANUFACTURER") "Nexperia USA Inc.")
        (field (name "INTERNAL PART NUMBER") "EICNUSOT666-06-0004")
      )
      (libsource (lib "Automobile-ML") (part "EICNUSOT666-06-0004"))
    )
    (comp (ref "VCC_IN")
      (value "Test Point- 35mil")
      (footprint "TP_35M_DIA")
      (fields (field (name "INTERNAL PART NUMBER") "EMS-TP35MIL-S"))
      (libsource (lib "Integrated_Master_Library") (part "EMS-TP35MIL-S"))
    )
  )
  (nets
    (net (code "1") (name "/AUTOMATIC") (class "Default")
      (node (ref "A") (pin "1") (pinfunction "1_1") (pintype "passive"))
      (node (ref "R4") (pin "2") (pinfunction "2_2") (pintype "passive"))
      (node (ref "U1") (pin "1") (pinfunction "PD4(HS)/[LINUART_CK]_TIM5_CH1/BEEP_1") (pintype "passive"))
      (node (ref "U3") (pin "2") (pinfunction "Q_2") (pintype "output"))
    )
    (net (code "2") (name "/M+") (class "Default")
      (node (ref "M+") (pin "1") (pinfunction "1_1") (pintype "passive"))
      (node (ref "R13") (pin "2") (pinfunction "2_2") (pintype "passive"))
      (node (ref "U1") (pin "19") (pinfunction "PD2_(HS)/AIN3_[TIM5_CH3]_19") (pintype "passive"))
      (node (ref "U6") (pin "2") (pinfunction "Q_2") (pintype "output"))
    )
    (net (code "3") (name "/M-") (class "Default")
      (node (ref "M-") (pin "1") (pinfunction "1_1") (pintype "passive"))
      (node (ref "R3") (pin "2") (pinfunction "2_2") (pintype "passive"))
      (node (ref "U1") (pin "13") (pinfunction "PC3_(HS)/TIM1_CH3_[TLI][TIM1_CH1N]_13") (pintype "passive"))
      (node (ref "U2") (pin "2") (pinfunction "Q_2") (pintype "output"))
    )
    (net (code "4") (name "/MANUAL") (class "Default")
      (node (ref "M") (pin "1") (pinfunction "1_1") (pintype "passive"))
      (node (ref "R9") (pin "2") (pinfunction "2_2") (pintype "passive"))
      (node (ref "U1") (pin "16") (pinfunction "PC6_(HS)/SPI_MOSI_[TIM1_CH1]_16") (pintype "passive"))
      (node (ref "U4") (pin "2") (pinfunction "Q_2") (pintype "output"))
    )
    (net (code "5") (name "/NEUTRAL") (class "Default")
      (node (ref "N") (pin "1") (pinfunction "1_1") (pintype "passive"))
      (node (ref "R10") (pin "2") (pinfunction "2_2") (pintype "passive"))
      (node (ref "U1") (pin "10") (pinfunction "PA3_(HS)/[SPI_NSS]_TIM5_CH3_10") (pintype "passive"))
      (node (ref "U5") (pin "2") (pinfunction "Q_2") (pintype "output"))
    )
    (net (code "6") (name "/REVERSE") (class "Default")
      (node (ref "R") (pin "1") (pinfunction "1_1") (pintype "passive"))
      (node (ref "R14") (pin "2") (pinfunction "2_2") (pintype "passive"))
      (node (ref "U1") (pin "20") (pinfunction "PD3_(HS)/AIN4/TIM5_CH2/ADC_ETR_20") (pintype "passive"))
      (node (ref "U7") (pin "2") (pinfunction "Q_2") (pintype "output"))
    )
    (net (code "7") (name "/S1") (class "Default")
      (node (ref "U1") (pin "14") (pinfunction "PC4_(HS)/TIM1_CH4/CLK_CCO/AIN2_[TIM1_CH2N]_14") (pintype "passive"))
      (node (ref "U9") (pin "5") (pinfunction "G2_5") (pintype "passive"))
    )
    (net (code "8") (name "/S2") (class "Default")
      (node (ref "U1") (pin "11") (pinfunction "PB5_(T)/I2C_SDA_[TIM1_BKIN]_11") (pintype "passive"))
      (node (ref "U10") (pin "5") (pinfunction "G2_5") (pintype "passive"))
    )
    (net (code "9") (name "/S3") (class "Default")
      (node (ref "U1") (pin "12") (pinfunction "PB4_(T)/I2C_SCL_[ADC_ETR]_12") (pintype "passive"))
      (node (ref "U10") (pin "2") (pinfunction "G1_2") (pintype "passive"))
    )
    (net (code "10") (name "/S4") (class "Default")
      (node (ref "U1") (pin "15") (pinfunction "PC5_(HS)/SPI_SCK_[TIM5_CH1]_15") (pintype "passive"))
      (node (ref "U9") (pin "2") (pinfunction "G1_2") (pintype "passive"))
    )
    (net (code "11") (name "/SIGNAL1") (class "Default")
      (node (ref "A1") (pin "1") (pinfunction "1_1") (pintype "passive"))
      (node (ref "D11") (pin "2") (pinfunction "CATHODE_2") (pintype "passive"))
      (node (ref "J3") (pin "4") (pinfunction "4_4") (pintype "passive"))
      (node (ref "SB2") (pin "2") (pinfunction "2_2") (pintype "passive"))
    )
    (net (code "12") (name "/SIGNAL2") (class "Default")
      (node (ref "A2") (pin "1") (pinfunction "1_1") (pintype "passive"))
      (node (ref "D5") (pin "2") (pinfunction "CATHODE_2") (pintype "passive"))
      (node (ref "J3") (pin "5") (pinfunction "5_5") (pintype "passive"))
      (node (ref "SB3") (pin "2") (pinfunction "2_2") (pintype "passive"))
    )
    (net (code "13") (name "/SIGNAL3") (class "Default")
      (node (ref "A3") (pin "1") (pinfunction "1_1") (pintype "passive"))
      (node (ref "D4") (pin "2") (pinfunction "CATHODE_2") (pintype "passive"))
      (node (ref "J3") (pin "6") (pinfunction "6_6") (pintype "passive"))
      (node (ref "SB5") (pin "2") (pinfunction "2_2") (pintype "passive"))
    )
    (net (code "14") (name "/SIGNAL4") (class "Default")
      (node (ref "A4") (pin "1") (pinfunction "1_1") (pintype "passive"))
      (node (ref "D10") (pin "2") (pinfunction "CATHODE_2") (pintype "passive"))
      (node (ref "J3") (pin "2") (pinfunction "2_2") (pintype "passive"))
      (node (ref "SB4") (pin "2") (pinfunction "2_2") (pintype "passive"))
    )
    (net (code "15") (name "/SWIM") (class "Default")
      (node (ref "D12") (pin "2") (pinfunction "CATHODE_2") (pintype "passive"))
      (node (ref "J1") (pin "5") (pinfunction "5_5") (pintype "passive"))
      (node (ref "U1") (pin "18") (pinfunction "PD1_(HS)/SWIM_18") (pintype "passive"))
    )
    (net (code "16") (name "/UART_RX") (class "Default")
      (node (ref "D13") (pin "2") (pinfunction "CATHODE_2") (pintype "passive"))
      (node (ref "J1") (pin "4") (pinfunction "4_4") (pintype "passive"))
      (node (ref "U1") (pin "3") (pinfunction "PD6_(HS)/AIN6/LINUART_RX_3") (pintype "passive"))
    )
    (net (code "17") (name "/UART_TX") (class "Default")
      (node (ref "D14") (pin "2") (pinfunction "CATHODE_2") (pintype "passive"))
      (node (ref "J1") (pin "6") (pinfunction "6_6") (pintype "passive"))
      (node (ref "U1") (pin "2") (pinfunction "PD5_(HS)/AIN5/LINUART_TX_2") (pintype "passive"))
    )
    (net (code "18") (name "/nRESET") (class "Default")
      (node (ref "C6") (pin "1") (pinfunction "1_1") (pintype "passive"))
      (node (ref "R5") (pin "1") (pinfunction "1_1") (pintype "passive"))
      (node (ref "R6") (pin "2") (pinfunction "2_2") (pintype "passive"))
      (node (ref "U1") (pin "4") (pinfunction "NRST_4") (pintype "passive"))
    )
    (net (code "19") (name "GND") (class "Default")
      (node (ref "C1") (pin "2") (pinfunction "2_2") (pintype "passive"))
      (node (ref "C10") (pin "1") (pinfunction "1_1") (pintype "passive"))
      (node (ref "C11") (pin "1") (pinfunction "1_1") (pintype "passive"))
      (node (ref "C12") (pin "2") (pinfunction "2_2") (pintype "passive"))
      (node (ref "C14") (pin "1") (pinfunction "1_1") (pintype "passive"))
      (node (ref "C15") (pin "2") (pinfunction "2_2") (pintype "passive"))
      (node (ref "C17") (pin "2") (pinfunction "2_2") (pintype "passive"))
      (node (ref "C18") (pin "2") (pinfunction "2_2") (pintype "passive"))
      (node (ref "C19") (pin "1") (pinfunction "1_1") (pintype "passive"))
      (node (ref "C2") (pin "1") (pinfunction "1_1") (pintype "passive"))
      (node (ref "C20") (pin "1") (pinfunction "1_1") (pintype "passive"))
      (node (ref "C21") (pin "1") (pinfunction "1_1") (pintype "passive"))
      (node (ref "C22") (pin "1") (pinfunction "1_1") (pintype "passive"))
      (node (ref "C23") (pin "1") (pinfunction "1_1") (pintype "passive"))
      (node (ref "C24") (pin "2") (pinfunction "2_2") (pintype "passive"))
      (node (ref "C25") (pin "2") (pinfunction "2_2") (pintype "passive"))
      (node (ref "C26") (pin "2") (pinfunction "2_2") (pintype "passive"))
      (node (ref "C3") (pin "2") (pinfunction "2_2") (pintype "passive"))
      (node (ref "C4") (pin "1") (pinfunction "1_1") (pintype "passive"))
      (node (ref "C5") (pin "1") (pinfunction "1_1") (pintype "passive"))
      (node (ref "C6") (pin "2") (pinfunction "2_2") (pintype "passive"))
      (node (ref "C7") (pin "1") (pinfunction "1_1") (pintype "passive"))
      (node (ref "C8") (pin "1") (pinfunction "1_1") (pintype "passive"))
      (node (ref "C9") (pin "1") (pinfunction "1_1") (pintype "passive"))
      (node (ref "D1") (pin "1") (pinfunction "Cathode_1") (pintype "passive"))
      (node (ref "D10") (pin "1") (pinfunction "ANODE_1") (pintype "passive"))
      (node (ref "D11") (pin "1") (pinfunction "ANODE_1") (pintype "passive"))
      (node (ref "D12") (pin "1") (pinfunction "ANODE_1") (pintype "passive"))
      (node (ref "D13") (pin "1") (pinfunction "ANODE_1") (pintype "passive"))
      (node (ref "D14") (pin "1") (pinfunction "ANODE_1") (pintype "passive"))
      (node (ref "D15") (pin "1") (pinfunction "ANODE_1") (pintype "passive"))
      (node (ref "D4") (pin "1") (pinfunction "ANODE_1") (pintype "passive"))
      (node (ref "D5") (pin "1") (pinfunction "ANODE_1") (pintype "passive"))
      (node (ref "D7") (pin "1") (pinfunction "ANODE_1") (pintype "passive"))
      (node (ref "GND") (pin "1") (pinfunction "1_1") (pintype "passive"))
      (node (ref "J1") (pin "3") (pinfunction "3_3") (pintype "passive"))
      (node (ref "J1") (pin "8") (pinfunction "8_8") (pintype "passive"))
      (node (ref "R16") (pin "1") (pinfunction "1_1") (pintype "passive"))
      (node (ref "R19") (pin "2") (pinfunction "2_2") (pintype "passive"))
      (node (ref "R20") (pin "2") (pinfunction "2_2") (pintype "passive"))
      (node (ref "R25") (pin "2") (pinfunction "2_2") (pintype "passive"))
      (node (ref "R26") (pin "2") (pinfunction "2_2") (pintype "passive"))
      (node (ref "SB1") (pin "2") (pinfunction "2_2") (pintype "passive"))
      (node (ref "U1") (pin "7") (pinfunction "VSS_7") (pintype "passive"))
      (node (ref "U2") (pin "3") (pinfunction "GND_3") (pintype "power_in"))
      (node (ref "U3") (pin "3") (pinfunction "GND_3") (pintype "power_in"))
      (node (ref "U4") (pin "3") (pinfunction "GND_3") (pintype "power_in"))
      (node (ref "U5") (pin "3") (pinfunction "GND_3") (pintype "power_in"))
      (node (ref "U6") (pin "3") (pinfunction "GND_3") (pintype "power_in"))
      (node (ref "U7") (pin "3") (pinfunction "GND_3") (pintype "power_in"))
      (node (ref "U8") (pin "1") (pinfunction "SYNC_1") (pintype "passive"))
      (node (ref "U8") (pin "2") (pinfunction "GND_2") (pintype "passive"))
      (node (ref "U8") (pin "9") (pinfunction "EPAD_9") (pintype "passive"))
    )
    (net (code "20") (name "Net-(C13-Pad2)") (class "Default")
      (node (ref "C13") (pin "2") (pinfunction "2_2") (pintype "passive"))
      (node (ref "R16") (pin "2") (pinfunction "2_2") (pintype "passive"))
    )
    (net (code "21") (name "Net-(C20-Pad2)") (class "Default")
      (node (ref "C20") (pin "2") (pinfunction "2_2") (pintype "passive"))
      (node (ref "R17") (pin "2") (pinfunction "2_2") (pintype "passive"))
      (node (ref "R19") (pin "1") (pinfunction "1_1") (pintype "passive"))
      (node (ref "SB5") (pin "1") (pinfunction "1_1") (pintype "passive"))
    )
    (net (code "22") (name "Net-(C21-Pad2)") (class "Default")
      (node (ref "C21") (pin "2") (pinfunction "2_2") (pintype "passive"))
      (node (ref "R18") (pin "2") (pinfunction "2_2") (pintype "passive"))
      (node (ref "R20") (pin "1") (pinfunction "1_1") (pintype "passive"))
      (node (ref "SB3") (pin "1") (pinfunction "1_1") (pintype "passive"))
    )
    (net (code "23") (name "Net-(C22-Pad2)") (class "Default")
      (node (ref "C22") (pin "2") (pinfunction "2_2") (pintype "passive"))
      (node (ref "R23") (pin "2") (pinfunction "2_2") (pintype "passive"))
      (node (ref "R25") (pin "1") (pinfunction "1_1") (pintype "passive"))
      (node (ref "SB4") (pin "1") (pinfunction "1_1") (pintype "passive"))
    )
    (net (code "24") (name "Net-(C23-Pad2)") (class "Default")
      (node (ref "C23") (pin "2") (pinfunction "2_2") (pintype "passive"))
      (node (ref "R24") (pin "2") (pinfunction "2_2") (pintype "passive"))
      (node (ref "R26") (pin "1") (pinfunction "1_1") (pintype "passive"))
      (node (ref "SB2") (pin "1") (pinfunction "1_1") (pintype "passive"))
    )
    (net (code "25") (name "Net-(D1-Anode)") (class "Default")
      (node (ref "C16") (pin "2") (pinfunction "2_2") (pintype "passive"))
      (node (ref "D1") (pin "2") (pinfunction "Anode_2") (pintype "passive"))
      (node (ref "L1") (pin "1") (pinfunction "1_1") (pintype "passive"))
      (node (ref "U8") (pin "6") (pinfunction "BUO_6") (pintype "passive"))
    )
    (net (code "26") (name "Net-(D2-ANODE)") (class "Default")
      (node (ref "D2") (pin "2") (pinfunction "ANODE_2") (pintype "passive"))
      (node (ref "U10") (pin "6") (pinfunction "D1_6") (pintype "passive"))
    )
    (net (code "27") (name "Net-(D2-CATHODE)") (class "Default")
      (node (ref "D2") (pin "1") (pinfunction "CATHODE_1") (pintype "passive"))
      (node (ref "R17") (pin "1") (pinfunction "1_1") (pintype "passive"))
    )
    (net (code "28") (name "Net-(D3-ANODE)") (class "Default")
      (node (ref "D3") (pin "2") (pinfunction "ANODE_2") (pintype "passive"))
      (node (ref "U10") (pin "3") (pinfunction "D2_3") (pintype "passive"))
    )
    (net (code "29") (name "Net-(D3-CATHODE)") (class "Default")
      (node (ref "D3") (pin "1") (pinfunction "CATHODE_1") (pintype "passive"))
      (node (ref "R18") (pin "1") (pinfunction "1_1") (pintype "passive"))
    )
    (net (code "30") (name "Net-(D6-Anode)") (class "Default")
      (node (ref "C17") (pin "1") (pinfunction "1_1") (pintype "passive"))
      (node (ref "D6") (pin "2") (pinfunction "Anode_2") (pintype "passive"))
      (node (ref "R21") (pin "2") (pinfunction "2_2") (pintype "passive"))
      (node (ref "R22") (pin "2") (pinfunction "2_2") (pintype "passive"))
    )
    (net (code "31") (name "Net-(D7-CATHODE)") (class "Default")
      (node (ref "D7") (pin "2") (pinfunction "CATHODE_2") (pintype "passive"))
      (node (ref "J3") (pin "3") (pinfunction "3_3") (pintype "passive"))
      (node (ref "SB6") (pin "1") (pinfunction "1_1") (pintype "passive"))
    )
    (net (code "32") (name "Net-(D8-ANODE)") (class "Default")
      (node (ref "D8") (pin "2") (pinfunction "ANODE_2") (pintype "passive"))
      (node (ref "U9") (pin "6") (pinfunction "D1_6") (pintype "passive"))
    )
    (net (code "33") (name "Net-(D8-CATHODE)") (class "Default")
      (node (ref "D8") (pin "1") (pinfunction "CATHODE_1") (pintype "passive"))
      (node (ref "R23") (pin "1") (pinfunction "1_1") (pintype "passive"))
    )
    (net (code "34") (name "Net-(D9-ANODE)") (class "Default")
      (node (ref "D9") (pin "2") (pinfunction "ANODE_2") (pintype "passive"))
      (node (ref "U9") (pin "3") (pinfunction "D2_3") (pintype "passive"))
    )
    (net (code "35") (name "Net-(D9-CATHODE)") (class "Default")
      (node (ref "D9") (pin "1") (pinfunction "CATHODE_1") (pintype "passive"))
      (node (ref "R24") (pin "1") (pinfunction "1_1") (pintype "passive"))
    )
    (net (code "36") (name "Net-(D15-CATHODE)") (class "Default")
      (node (ref "D15") (pin "2") (pinfunction "CATHODE_2") (pintype "passive"))
      (node (ref "J1") (pin "7") (pinfunction "7_7") (pintype "passive"))
      (node (ref "R6") (pin "1") (pinfunction "1_1") (pintype "passive"))
    )
    (net (code "37") (name "Net-(J3-Pad1)") (class "Default")
      (node (ref "J3") (pin "1") (pinfunction "1_1") (pintype "passive"))
      (node (ref "SB1") (pin "1") (pinfunction "1_1") (pintype "passive"))
    )
    (net (code "38") (name "Net-(R21-Pad1)") (class "Default")
      (node (ref "R21") (pin "1") (pinfunction "1_1") (pintype "passive"))
      (node (ref "R22") (pin "1") (pinfunction "1_1") (pintype "passive"))
      (node (ref "SB6") (pin "2") (pinfunction "2_2") (pintype "passive"))
    )
    (net (code "39") (name "Net-(U1-VCAP)") (class "Default")
      (node (ref "C3") (pin "1") (pinfunction "1_1") (pintype "passive"))
      (node (ref "U1") (pin "8") (pinfunction "VCAP_8") (pintype "passive"))
    )
    (net (code "40") (name "Net-(U2-VDD)") (class "Default")
      (node (ref "C4") (pin "2") (pinfunction "2_2") (pintype "passive"))
      (node (ref "R1") (pin "1") (pinfunction "1_1") (pintype "passive"))
      (node (ref "U2") (pin "1") (pinfunction "VDD_1") (pintype "power_in"))
    )
    (net (code "41") (name "Net-(U3-VDD)") (class "Default")
      (node (ref "C5") (pin "2") (pinfunction "2_2") (pintype "passive"))
      (node (ref "R2") (pin "1") (pinfunction "1_1") (pintype "passive"))
      (node (ref "U3") (pin "1") (pinfunction "VDD_1") (pintype "power_in"))
    )
    (net (code "42") (name "Net-(U4-VDD)") (class "Default")
      (node (ref "C7") (pin "2") (pinfunction "2_2") (pintype "passive"))
      (node (ref "R7") (pin "1") (pinfunction "1_1") (pintype "passive"))
      (node (ref "U4") (pin "1") (pinfunction "VDD_1") (pintype "power_in"))
    )
    (net (code "43") (name "Net-(U5-VDD)") (class "Default")
      (node (ref "C8") (pin "2") (pinfunction "2_2") (pintype "passive"))
      (node (ref "R8") (pin "1") (pinfunction "1_1") (pintype "passive"))
      (node (ref "U5") (pin "1") (pinfunction "VDD_1") (pintype "power_in"))
    )
    (net (code "44") (name "Net-(U6-VDD)") (class "Default")
      (node (ref "C9") (pin "2") (pinfunction "2_2") (pintype "passive"))
      (node (ref "R11") (pin "1") (pinfunction "1_1") (pintype "passive"))
      (node (ref "U6") (pin "1") (pinfunction "VDD_1") (pintype "power_in"))
    )
    (net (code "45") (name "Net-(U7-VDD)") (class "Default")
      (node (ref "C10") (pin "2") (pinfunction "2_2") (pintype "passive"))
      (node (ref "R12") (pin "1") (pinfunction "1_1") (pintype "passive"))
      (node (ref "U7") (pin "1") (pinfunction "VDD_1") (pintype "power_in"))
    )
    (net (code "46") (name "Net-(U8-BDS)") (class "Default")
      (node (ref "C16") (pin "1") (pinfunction "1_1") (pintype "passive"))
      (node (ref "U8") (pin "5") (pinfunction "BDS_5") (pintype "passive"))
    )
    (net (code "47") (name "Net-(U8-COMP)") (class "Default")
      (node (ref "C13") (pin "1") (pinfunction "1_1") (pintype "passive"))
      (node (ref "C24") (pin "1") (pinfunction "1_1") (pintype "passive"))
      (node (ref "U8") (pin "3") (pinfunction "COMP_3") (pintype "passive"))
    )
    (net (code "48") (name "Net-(U8-EN)") (class "Default")
      (node (ref "R15") (pin "1") (pinfunction "1_1") (pintype "passive"))
      (node (ref "U8") (pin "7") (pinfunction "EN_7") (pintype "passive"))
    )
    (net (code "49") (name "Net-(U8-FB)") (class "Default")
      (node (ref "C14") (pin "2") (pinfunction "2_2") (pintype "passive"))
      (node (ref "C19") (pin "2") (pinfunction "2_2") (pintype "passive"))
      (node (ref "FB1") (pin "1") (pinfunction "1_1") (pintype "passive"))
      (node (ref "L1") (pin "2") (pinfunction "2_2") (pintype "passive"))
      (node (ref "U8") (pin "4") (pinfunction "FB_4") (pintype "passive"))
    )
    (net (code "50") (name "VCC_5V") (class "Default")
      (node (ref "5V") (pin "1") (pinfunction "1_1") (pintype "passive"))
      (node (ref "C1") (pin "1") (pinfunction "1_1") (pintype "passive"))
      (node (ref "C15") (pin "1") (pinfunction "1_1") (pintype "passive"))
      (node (ref "C2") (pin "2") (pinfunction "2_2") (pintype "passive"))
      (node (ref "C25") (pin "1") (pinfunction "1_1") (pintype "passive"))
      (node (ref "C26") (pin "1") (pinfunction "1_1") (pintype "passive"))
      (node (ref "FB1") (pin "2") (pinfunction "2_2") (pintype "passive"))
      (node (ref "J1") (pin "1") (pinfunction "1_1") (pintype "passive"))
      (node (ref "J1") (pin "2") (pinfunction "2_2") (pintype "passive"))
      (node (ref "R1") (pin "2") (pinfunction "2_2") (pintype "passive"))
      (node (ref "R10") (pin "1") (pinfunction "1_1") (pintype "passive"))
      (node (ref "R11") (pin "2") (pinfunction "2_2") (pintype "passive"))
      (node (ref "R12") (pin "2") (pinfunction "2_2") (pintype "passive"))
      (node (ref "R13") (pin "1") (pinfunction "1_1") (pintype "passive"))
      (node (ref "R14") (pin "1") (pinfunction "1_1") (pintype "passive"))
      (node (ref "R2") (pin "2") (pinfunction "2_2") (pintype "passive"))
      (node (ref "R3") (pin "1") (pinfunction "1_1") (pintype "passive"))
      (node (ref "R4") (pin "1") (pinfunction "1_1") (pintype "passive"))
      (node (ref "R5") (pin "2") (pinfunction "2_2") (pintype "passive"))
      (node (ref "R7") (pin "2") (pinfunction "2_2") (pintype "passive"))
      (node (ref "R8") (pin "2") (pinfunction "2_2") (pintype "passive"))
      (node (ref "R9") (pin "1") (pinfunction "1_1") (pintype "passive"))
      (node (ref "U1") (pin "9") (pinfunction "VDD_9") (pintype "passive"))
      (node (ref "U10") (pin "1") (pinfunction "S1_1") (pintype "passive"))
      (node (ref "U10") (pin "4") (pinfunction "S2_4") (pintype "passive"))
      (node (ref "U9") (pin "1") (pinfunction "S1_1") (pintype "passive"))
      (node (ref "U9") (pin "4") (pinfunction "S2_4") (pintype "passive"))
    )
    (net (code "51") (name "VCC_IN") (class "Default")
      (node (ref "C11") (pin "2") (pinfunction "2_2") (pintype "passive"))
      (node (ref "C12") (pin "1") (pinfunction "1_1") (pintype "passive"))
      (node (ref "C18") (pin "1") (pinfunction "1_1") (pintype "passive"))
      (node (ref "D6") (pin "1") (pinfunction "Cathode_1") (pintype "passive"))
      (node (ref "R15") (pin "2") (pinfunction "2_2") (pintype "passive"))
      (node (ref "U8") (pin "8") (pinfunction "VS_8") (pintype "passive"))
      (node (ref "VCC_IN") (pin "1") (pinfunction "1_1") (pintype "passive"))
    )
    (net (code "52") (name "unconnected-(FID1-Pad0)") (class "Default")
      (node (ref "FID1") (pin "0") (pinfunction "0_0") (pintype "passive+no_connect"))
    )
    (net (code "53") (name "unconnected-(FID2-Pad0)") (class "Default")
      (node (ref "FID2") (pin "0") (pinfunction "0_0") (pintype "passive+no_connect"))
    )
    (net (code "54") (name "unconnected-(FID3-Pad0)") (class "Default")
      (node (ref "FID3") (pin "0") (pinfunction "0_0") (pintype "passive+no_connect"))
    )
    (net (code "55") (name "unconnected-(FID4-Pad0)") (class "Default")
      (node (ref "FID4") (pin "0") (pinfunction "0_0") (pintype "passive+no_connect"))
    )
    (net (code "56") (name "unconnected-(U1-PA1{slash}OSCIN-Pad5)") (class "Default")
      (node (ref "U1") (pin "5") (pinfunction "PA1/OSCIN_5") (pintype "passive+no_connect"))
    )
    (net (code "57") (name "unconnected-(U1-PA2{slash}OSCOUT-Pad6)") (class "Default")
      (node (ref "U1") (pin "6") (pinfunction "PA2/OSCOUT_6") (pintype "passive+no_connect"))
    )
    (net (code "58") (name "unconnected-(U1-PC7_(HS){slash}SPI_MISO_[TIM1_CH2]-Pad17)") (class "Default")
      (node (ref "U1") (pin "17") (pinfunction "PC7_(HS)/SPI_MISO_[TIM1_CH2]_17") (pintype "passive+no_connect"))
    )
  )
)
